# MCU_Power_Supply_Accel.net
KiCad netlist of a schematic drawn in Altium Designer
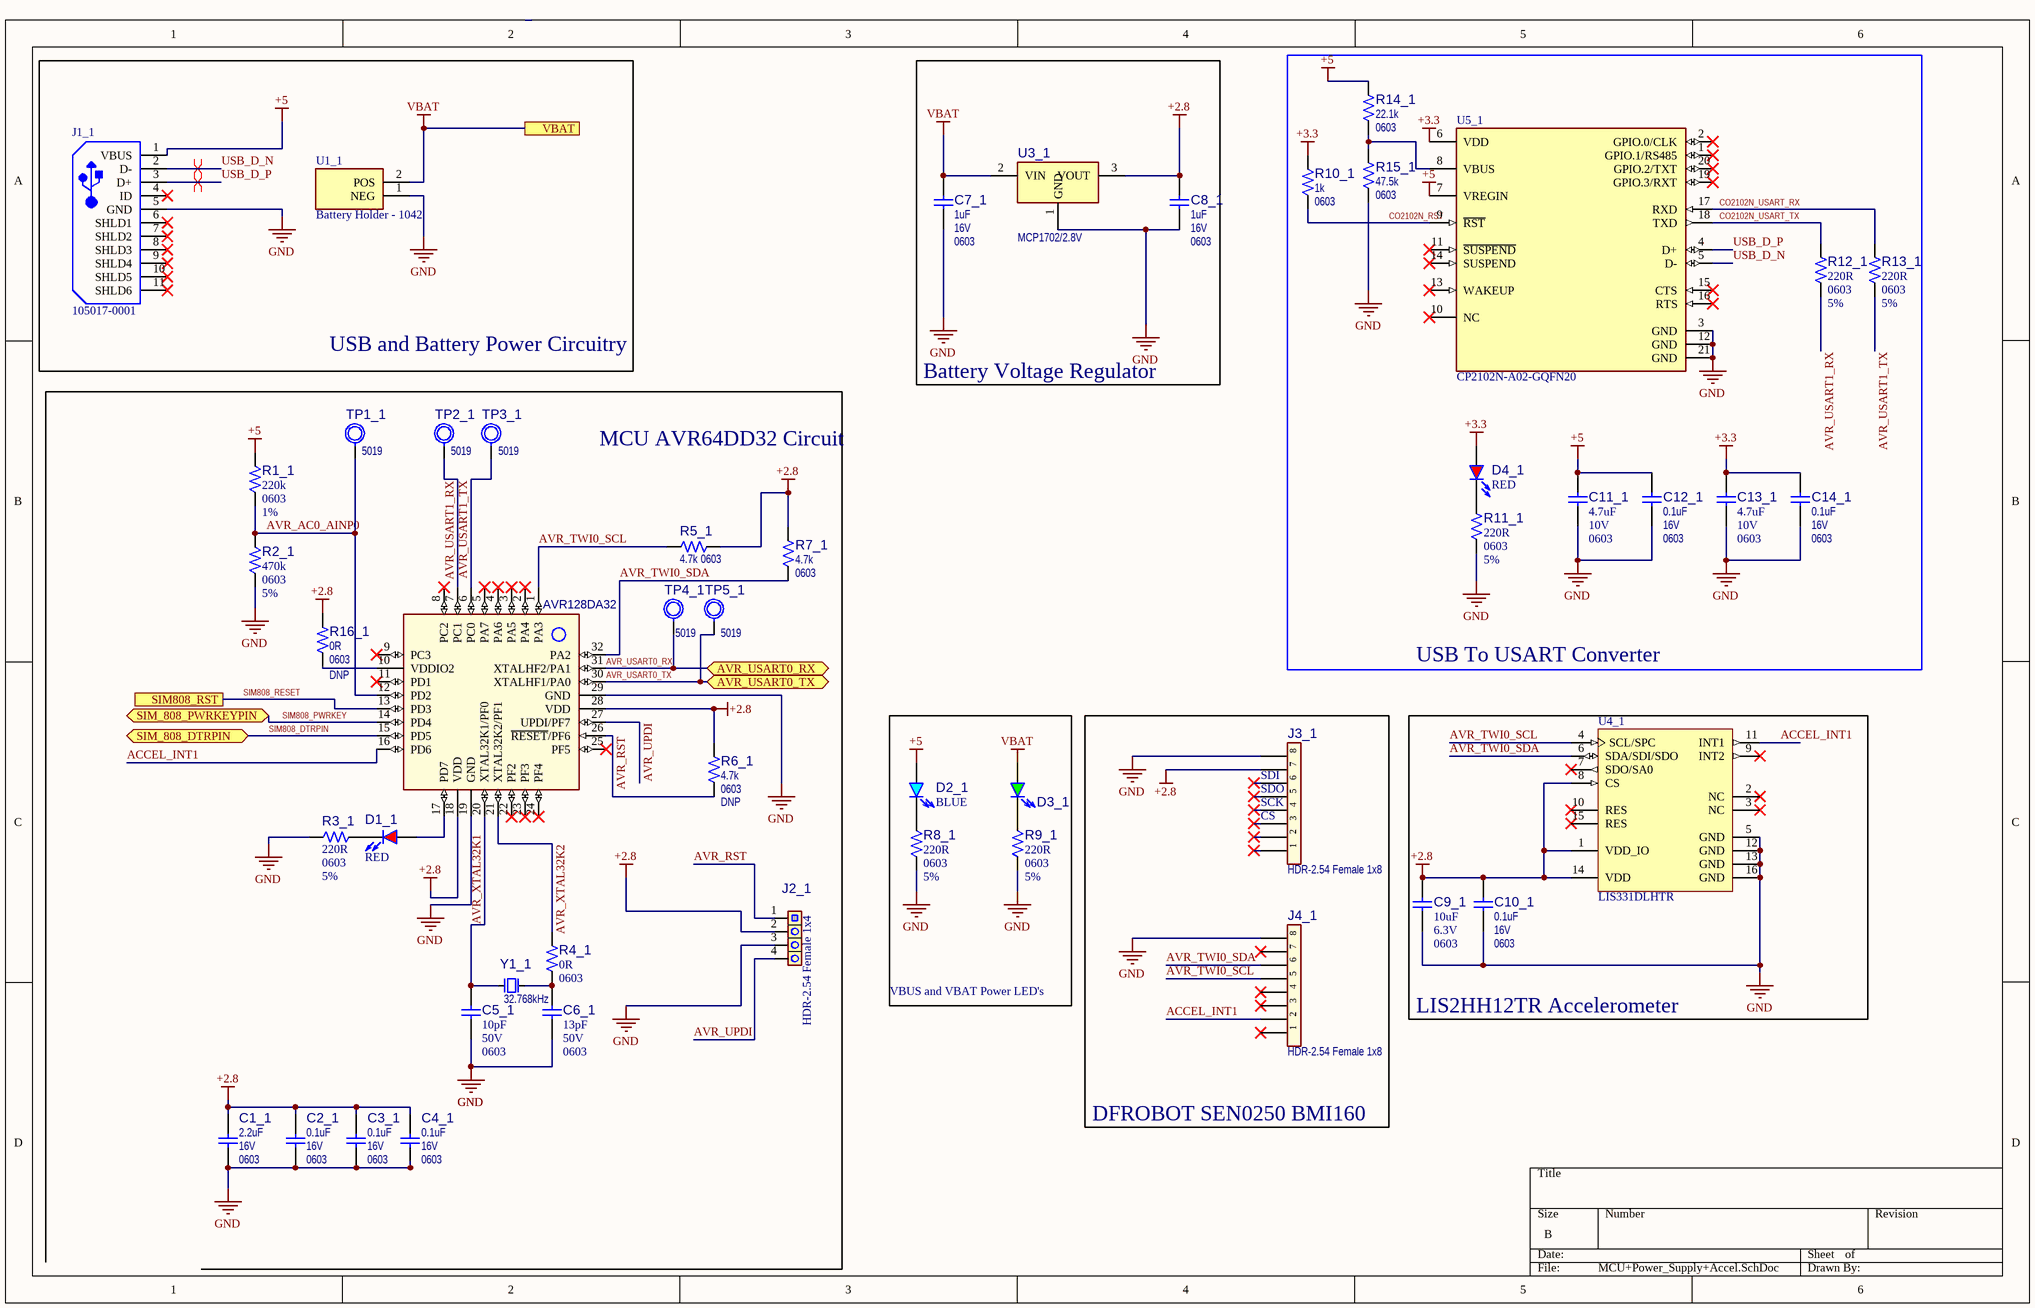
[diagram p0: MCU+Power_Supply+Accel.SchDoc]

(export (version "E")
  (design (tool "Eeschema 10.0.6"))
  (components
    (comp (ref "AVR128DA32")
      (value "AVR128DA32-E/PT")
      (footprint "TQFP-32_7x7")
      (fields (field (name "OWNER") "Simen Tanbergmoen"))
      (libsource (lib "MCHP-CDB-Offline") (part "AVR64DD32 TQFP-32"))
    )
    (comp (ref "C1_1")
      (value "2.2uF")
      (footprint "CAP_C_0603")
      (fields
        (field (name "VOLTAGE") "16V")
        (field (name "PACKAGE") "0603")
        (field (name "TOLERANCE") "10%")
        (field (name "Comment") "Capacitor NP")
      )
      (libsource (lib "MCHP-CDB") (part "Capacitor NP"))
    )
    (comp (ref "C2_1")
      (value "0.1uF")
      (footprint "CAP_C_0603")
      (fields
        (field (name "VOLTAGE") "16V")
        (field (name "PACKAGE") "0603")
        (field (name "TOLERANCE") "10%")
        (field (name "Comment") "Capacitor NP")
        (field (name "OWNER") "Cristian Papuc")
      )
      (libsource (lib "MCHP-CDB") (part "Capacitor NP"))
    )
    (comp (ref "C3_1")
      (value "0.1uF")
      (footprint "CAP_C_0603")
      (fields
        (field (name "VOLTAGE") "16V")
        (field (name "PACKAGE") "0603")
        (field (name "TOLERANCE") "10%")
        (field (name "Comment") "Capacitor NP")
        (field (name "OWNER") "Cristian Papuc")
      )
      (libsource (lib "MCHP-CDB") (part "Capacitor NP"))
    )
    (comp (ref "C4_1")
      (value "0.1uF")
      (footprint "CAP_C_0603")
      (fields
        (field (name "VOLTAGE") "16V")
        (field (name "PACKAGE") "0603")
        (field (name "TOLERANCE") "10%")
        (field (name "Comment") "Capacitor NP")
        (field (name "OWNER") "Cristian Papuc")
      )
      (libsource (lib "MCHP-CDB") (part "Capacitor NP"))
    )
    (comp (ref "C5_1")
      (value "10pF")
      (footprint "CAP_C_0603")
      (fields
        (field (name "VOLTAGE") "50V")
        (field (name "PACKAGE") "0603")
        (field (name "TOLERANCE") "5%")
        (field (name "Comment") "Capacitor NP")
        (field (name "OWNER") "Cristina Salanti")
      )
      (libsource (lib "MCHP-CDB") (part "Capacitor NP"))
    )
    (comp (ref "C6_1")
      (value "13pF")
      (footprint "CAP_C_0603")
      (fields
        (field (name "VOLTAGE") "50V")
        (field (name "PACKAGE") "0603")
        (field (name "TOLERANCE") "2%")
        (field (name "Comment") "Capacitor NP")
        (field (name "OWNER") "Dragos Danaila")
      )
      (libsource (lib "MCHP-CDB") (part "Capacitor NP"))
    )
    (comp (ref "C7_1")
      (value "1uF")
      (footprint "CAP_C_0603")
      (fields
        (field (name "VOLTAGE") "16V")
        (field (name "PACKAGE") "0603")
        (field (name "TOLERANCE") "10%")
        (field (name "Comment") "Capacitor NP")
      )
      (libsource (lib "MCHP-CDB") (part "Capacitor NP"))
    )
    (comp (ref "C8_1")
      (value "1uF")
      (footprint "CAP_C_0603")
      (fields
        (field (name "VOLTAGE") "16V")
        (field (name "PACKAGE") "0603")
        (field (name "TOLERANCE") "10%")
        (field (name "Comment") "Capacitor NP")
      )
      (libsource (lib "MCHP-CDB") (part "Capacitor NP"))
    )
    (comp (ref "C9_1")
      (value "10uF")
      (footprint "CAP_C_0603")
      (fields
        (field (name "VOLTAGE") "6.3V")
        (field (name "PACKAGE") "0603")
        (field (name "TOLERANCE") "20%")
        (field (name "Comment") "Capacitor NP")
      )
      (libsource (lib "MCHP-CDB") (part "Capacitor NP"))
    )
    (comp (ref "C10_1")
      (value "0.1uF")
      (footprint "CAP_C_0603")
      (fields
        (field (name "VOLTAGE") "16V")
        (field (name "PACKAGE") "0603")
        (field (name "TOLERANCE") "10%")
        (field (name "Comment") "Capacitor NP")
        (field (name "OWNER") "Cristian Papuc")
      )
      (libsource (lib "MCHP-CDB") (part "Capacitor NP"))
    )
    (comp (ref "C11_1")
      (value "4.7uF")
      (footprint "CAP_C_0603")
      (fields
        (field (name "VOLTAGE") "10V")
        (field (name "PACKAGE") "0603")
        (field (name "TOLERANCE") "80%")
        (field (name "Comment") "Capacitor NP")
      )
      (libsource (lib "MCHP-CDB") (part "Capacitor NP"))
    )
    (comp (ref "C12_1")
      (value "0.1uF")
      (footprint "CAP_C_0603")
      (fields
        (field (name "VOLTAGE") "16V")
        (field (name "PACKAGE") "0603")
        (field (name "TOLERANCE") "10%")
        (field (name "Comment") "Capacitor NP")
        (field (name "OWNER") "Cristian Papuc")
      )
      (libsource (lib "MCHP-CDB") (part "Capacitor NP"))
    )
    (comp (ref "C13_1")
      (value "4.7uF")
      (footprint "CAP_C_0603")
      (fields
        (field (name "VOLTAGE") "10V")
        (field (name "PACKAGE") "0603")
        (field (name "TOLERANCE") "80%")
        (field (name "Comment") "Capacitor NP")
      )
      (libsource (lib "MCHP-CDB") (part "Capacitor NP"))
    )
    (comp (ref "C14_1")
      (value "0.1uF")
      (footprint "CAP_C_0603")
      (fields
        (field (name "VOLTAGE") "16V")
        (field (name "PACKAGE") "0603")
        (field (name "TOLERANCE") "10%")
        (field (name "Comment") "Capacitor NP")
        (field (name "OWNER") "Cristian Papuc")
      )
      (libsource (lib "MCHP-CDB") (part "Capacitor NP"))
    )
    (comp (ref "D1_1")
      (value "RED")
      (footprint "LED_0603_RED")
      (description "LED")
      (fields (field (name "POWER") "100mW") (field (name "Comment") "LED_red"))
      (libsource (lib "MCHP-CDB") (part "LED_red"))
    )
    (comp (ref "D2_1")
      (value "BLUE")
      (footprint "LED_0603_Blue")
      (description "LED")
      (fields
        (field (name "POWER") "76mW")
        (field (name "Comment") "LED_blue")
        (field (name "OWNER") "Tad Ahlvers")
      )
      (libsource (lib "MCHP-CDB") (part "LED_blue"))
    )
    (comp (ref "D3_1")
      (value "LED_green_true")
      (footprint "LED_0603_Green")
      (description "LED TRUE GREEN")
      (fields (field (name "OWNER") "Ed Kennedy"))
      (libsource (lib "MCHP-CDB") (part "LED_green_true"))
    )
    (comp (ref "D4_1")
      (value "RED")
      (footprint "LED_0603_RED")
      (description "LED")
      (fields (field (name "POWER") "100mW") (field (name "Comment") "LED_red"))
      (libsource (lib "MCHP-CDB") (part "LED_red"))
    )
    (comp (ref "J1_1")
      (value "105017-0001")
      (footprint "USB-MICRO-B_V")
      (fields (field (name "MANUFACTURER") "Molex"))
      (libsource (lib "Altium Content Vault") (part "USB-5-6SHLD"))
    )
    (comp (ref "J2_1")
      (value "HDR-2.54 Female 1x4")
      (footprint "HDR_F_2.54_1x4_U_TH_V_SAM_SSW-104-01-G-S")
      (fields (field (name "Comment") "Header 1x4") (field (name "OWNER") "Randolph Sobrepena"))
      (libsource (lib "MCHP-CDB") (part "Header 1x4"))
    )
    (comp (ref "J3_1")
      (value "HDR-2.54 Female 1x8")
      (footprint "HDR_F_2.54_1x8")
      (description "Header 1x8")
      (fields (field (name "OWNER") "Bogdan P (M91398)"))
      (libsource (lib "MCHP-CDB") (part "Header 1x8"))
    )
    (comp (ref "J4_1")
      (value "HDR-2.54 Female 1x8")
      (footprint "HDR_F_2.54_1x8")
      (description "Header 1x8")
      (fields (field (name "OWNER") "Bogdan P (M91398)"))
      (libsource (lib "MCHP-CDB") (part "Header 1x8"))
    )
    (comp (ref "R1_1")
      (value "220k")
      (footprint "RES_C_0603")
      (description "Resistor")
      (fields
        (field (name "PACKAGE") "0603")
        (field (name "TOLERANCE") "1%")
        (field (name "VOLTAGE") "75V")
        (field (name "POWER") "1/10W")
        (field (name "OWNER") "Adrian M (M91404)")
      )
      (libsource (lib "MCHP-CDB") (part "Resistor"))
    )
    (comp (ref "R2_1")
      (value "470k")
      (footprint "RES_C_0603")
      (description "Resistor")
      (fields
        (field (name "PACKAGE") "0603")
        (field (name "TOLERANCE") "5%")
        (field (name "VOLTAGE") "75V")
        (field (name "POWER") "1/10W")
        (field (name "OWNER") "Adrian T (M91397)")
      )
      (libsource (lib "MCHP-CDB") (part "Resistor"))
    )
    (comp (ref "R3_1")
      (value "220R")
      (footprint "RES_C_0603")
      (description "Resistor")
      (fields
        (field (name "PACKAGE") "0603")
        (field (name "TOLERANCE") "5%")
        (field (name "VOLTAGE") "50V")
        (field (name "POWER") "1/10W")
      )
      (libsource (lib "MCHP-CDB") (part "Resistor"))
    )
    (comp (ref "R4_1")
      (value "0R")
      (footprint "RES_C_0603")
      (description "Resistor")
      (fields
        (field (name "PACKAGE") "0603")
        (field (name "POWER") "1/10W")
        (field (name "OWNER") "Steve Dziaba")
      )
      (libsource (lib "MCHP-CDB") (part "Resistor"))
    )
    (comp (ref "R5_1")
      (value "4.7k")
      (footprint "RES_C_0603")
      (description "Resistor")
      (fields
        (field (name "PACKAGE") "0603")
        (field (name "VOLTAGE") "75V")
        (field (name "POWER") "1/10W")
        (field (name "OWNER") "Bogdan P (M91398)")
      )
      (libsource (lib "MCHP-CDB") (part "Resistor"))
    )
    (comp (ref "R6_1")
      (value "4.7k")
      (footprint "RES_C_0603")
      (description "Resistor")
      (fields
        (field (name "PACKAGE") "0603")
        (field (name "VOLTAGE") "75V")
        (field (name "POWER") "1/10W")
        (field (name "POPULATED") "DNP")
        (field (name "OWNER") "Bogdan P (M91398)")
      )
      (libsource (lib "MCHP-CDB") (part "Resistor"))
    )
    (comp (ref "R7_1")
      (value "4.7k")
      (footprint "RES_C_0603")
      (description "Resistor")
      (fields
        (field (name "PACKAGE") "0603")
        (field (name "VOLTAGE") "75V")
        (field (name "POWER") "1/10W")
        (field (name "OWNER") "Bogdan P (M91398)")
      )
      (libsource (lib "MCHP-CDB") (part "Resistor"))
    )
    (comp (ref "R8_1")
      (value "220R")
      (footprint "RES_C_0603")
      (description "Resistor")
      (fields
        (field (name "PACKAGE") "0603")
        (field (name "TOLERANCE") "5%")
        (field (name "VOLTAGE") "50V")
        (field (name "POWER") "1/10W")
      )
      (libsource (lib "MCHP-CDB") (part "Resistor"))
    )
    (comp (ref "R9_1")
      (value "220R")
      (footprint "RES_C_0603")
      (description "Resistor")
      (fields
        (field (name "PACKAGE") "0603")
        (field (name "TOLERANCE") "5%")
        (field (name "VOLTAGE") "50V")
        (field (name "POWER") "1/10W")
      )
      (libsource (lib "MCHP-CDB") (part "Resistor"))
    )
    (comp (ref "R10_1")
      (value "1k")
      (footprint "RES_C_0603")
      (description "Resistor")
      (fields
        (field (name "PACKAGE") "0603")
        (field (name "VOLTAGE") "75V")
        (field (name "POWER") "1/10W")
        (field (name "OWNER") "Tad Ahlvers")
      )
      (libsource (lib "MCHP-CDB") (part "Resistor"))
    )
    (comp (ref "R11_1")
      (value "220R")
      (footprint "RES_C_0603")
      (description "Resistor")
      (fields
        (field (name "PACKAGE") "0603")
        (field (name "TOLERANCE") "5%")
        (field (name "VOLTAGE") "50V")
        (field (name "POWER") "1/10W")
      )
      (libsource (lib "MCHP-CDB") (part "Resistor"))
    )
    (comp (ref "R12_1")
      (value "220R")
      (footprint "RES_C_0603")
      (description "Resistor")
      (fields
        (field (name "PACKAGE") "0603")
        (field (name "TOLERANCE") "5%")
        (field (name "VOLTAGE") "50V")
        (field (name "POWER") "1/10W")
      )
      (libsource (lib "MCHP-CDB") (part "Resistor"))
    )
    (comp (ref "R13_1")
      (value "220R")
      (footprint "RES_C_0603")
      (description "Resistor")
      (fields
        (field (name "PACKAGE") "0603")
        (field (name "TOLERANCE") "5%")
        (field (name "VOLTAGE") "50V")
        (field (name "POWER") "1/10W")
      )
      (libsource (lib "MCHP-CDB") (part "Resistor"))
    )
    (comp (ref "R14_1")
      (value "22.1k")
      (footprint "RES_C_0603")
      (description "Resistor")
      (fields
        (field (name "PACKAGE") "0603")
        (field (name "VOLTAGE") "75V")
        (field (name "POWER") "1/10W")
        (field (name "OWNER") "Kamatchi Sundaresan")
      )
      (libsource (lib "MCHP-CDB") (part "Resistor"))
    )
    (comp (ref "R15_1")
      (value "47.5k")
      (footprint "RES_C_0603")
      (description "Resistor")
      (fields
        (field (name "PACKAGE") "0603")
        (field (name "POWER") "1/10W")
        (field (name "OWNER") "Sam Charles")
      )
      (libsource (lib "MCHP-CDB") (part "Resistor"))
    )
    (comp (ref "R16_1")
      (value "0R")
      (footprint "RES_C_0603")
      (description "Resistor")
      (fields
        (field (name "PACKAGE") "0603")
        (field (name "POWER") "1/10W")
        (field (name "POPULATED") "DNP")
        (field (name "OWNER") "Steve Dziaba")
      )
      (libsource (lib "MCHP-CDB") (part "Resistor"))
    )
    (comp (ref "TP1_1")
      (value "5019")
      (footprint "TP_3.8x2.03_SMD")
      (description "Test Point")
      (fields (field (name "OWNER") "Jairuz Agang-ang"))
      (libsource (lib "MCHP-CDB") (part "Test Point"))
    )
    (comp (ref "TP2_1")
      (value "5019")
      (footprint "TP_3.8x2.03_SMD")
      (description "Test Point")
      (fields (field (name "OWNER") "Jairuz Agang-ang"))
      (libsource (lib "MCHP-CDB") (part "Test Point"))
    )
    (comp (ref "TP3_1")
      (value "5019")
      (footprint "TP_3.8x2.03_SMD")
      (description "Test Point")
      (fields (field (name "OWNER") "Jairuz Agang-ang"))
      (libsource (lib "MCHP-CDB") (part "Test Point"))
    )
    (comp (ref "TP4_1")
      (value "5019")
      (footprint "TP_3.8x2.03_SMD")
      (description "Test Point")
      (fields (field (name "OWNER") "Jairuz Agang-ang"))
      (libsource (lib "MCHP-CDB") (part "Test Point"))
    )
    (comp (ref "TP5_1")
      (value "5019")
      (footprint "TP_3.8x2.03_SMD")
      (description "Test Point")
      (fields (field (name "OWNER") "Jairuz Agang-ang"))
      (libsource (lib "MCHP-CDB") (part "Test Point"))
    )
    (comp (ref "U1_1")
      (value "Battery Holder - 1042")
      (footprint "SamacSys:KEYSTONE-1042")
      (description "Undefined or Miscellaneous")
      (fields (field (name "MANUFACTURER_PART_NUMBER") "1042") (field (name "MOUSER PART NUMBER") "534-1042"))
      (libsource (lib "*") (part "1042"))
    )
    (comp (ref "U3_1")
      (value "MCP1702/2.8V")
      (footprint "SOT-89-3")
      (description "LDO")
      (fields (field (name "Comment") "MCP170X SOT-89-3_TO-92-3"))
      (libsource (lib "MCHP-CDB") (part "MCP170X SOT-89-3_TO-92-3"))
    )
    (comp (ref "U4_1")
      (value "LIS331DLHTR")
      (footprint "STM-LGA16-3X3X1")
      (fields (field (name "MANUFACTURER") "STMicroelectronics"))
      (libsource (lib "Altium Content Vault") (part "SEN-MOT-LIS331DL-16"))
    )
    (comp (ref "U5_1")
      (value "CP2102N-A02-GQFN20")
      (footprint "FP-CP2102N-A02-GQFN20-MFG")
      (description "IC USB TO UART BRIDGE QFN20")
      (libsource (lib "Altium Content Vault") (part "535e9eb0fa6e07ebb008498c6833ade"))
    )
    (comp (ref "Y1_1")
      (value "32.768kHz")
      (footprint "CRYSTAL_FX135A_L3.2W1.5H0.9")
      (description "Crystal")
      (fields
        (field (name "TOLERANCE") "20ppm")
        (field (name "Comment") "Crystal 2 Pins")
        (field (name "OWNER") "Jesus Aviles")
      )
      (libsource (lib "MCHP-CDB") (part "Crystal 2 Pins"))
    )
  )
  (nets
    (net (code "1") (name "+2.8") (class "Default")
      (node (ref "AVR128DA32") (pin "18") (pinfunction "VDD_18") (pintype "power_in"))
      (node (ref "AVR128DA32") (pin "28") (pinfunction "VDD_28") (pintype "power_in"))
      (node (ref "C10_1") (pin "2") (pinfunction "2_2") (pintype "passive"))
      (node (ref "C1_1") (pin "2") (pinfunction "2_2") (pintype "passive"))
      (node (ref "C2_1") (pin "2") (pinfunction "2_2") (pintype "passive"))
      (node (ref "C3_1") (pin "2") (pinfunction "2_2") (pintype "passive"))
      (node (ref "C4_1") (pin "2") (pinfunction "2_2") (pintype "passive"))
      (node (ref "C8_1") (pin "2") (pinfunction "2_2") (pintype "passive"))
      (node (ref "C9_1") (pin "2") (pinfunction "2_2") (pintype "passive"))
      (node (ref "J2_1") (pin "2") (pinfunction "2_2") (pintype "passive"))
      (node (ref "J3_1") (pin "7") (pinfunction "7_7") (pintype "passive"))
      (node (ref "R16_1") (pin "1") (pinfunction "1_1") (pintype "passive"))
      (node (ref "R5_1") (pin "2") (pinfunction "2_2") (pintype "passive"))
      (node (ref "R6_1") (pin "2") (pinfunction "2_2") (pintype "passive"))
      (node (ref "R7_1") (pin "2") (pinfunction "2_2") (pintype "passive"))
      (node (ref "U3_1") (pin "3") (pinfunction "VOUT_3") (pintype "power_in"))
      (node (ref "U4_1") (pin "1") (pinfunction "VDD_IO_1") (pintype "power_in"))
      (node (ref "U4_1") (pin "14") (pinfunction "VDD_14") (pintype "power_in"))
      (node (ref "U4_1") (pin "8") (pinfunction "CS_8") (pintype "input"))
    )
    (net (code "2") (name "+3.3") (class "Default")
      (node (ref "C13_1") (pin "2") (pinfunction "2_2") (pintype "passive"))
      (node (ref "C14_1") (pin "2") (pinfunction "2_2") (pintype "passive"))
      (node (ref "D4_1") (pin "1") (pinfunction "A_1") (pintype "passive"))
      (node (ref "R10_1") (pin "2") (pinfunction "2_2") (pintype "passive"))
      (node (ref "U5_1") (pin "6") (pinfunction "VDD_6") (pintype "power_in"))
    )
    (net (code "3") (name "+5") (class "Default")
      (node (ref "C11_1") (pin "2") (pinfunction "2_2") (pintype "passive"))
      (node (ref "C12_1") (pin "2") (pinfunction "2_2") (pintype "passive"))
      (node (ref "D2_1") (pin "1") (pinfunction "A_1") (pintype "passive"))
      (node (ref "J1_1") (pin "1") (pinfunction "VBUS_1") (pintype "passive"))
      (node (ref "R14_1") (pin "2") (pinfunction "2_2") (pintype "passive"))
      (node (ref "R1_1") (pin "2") (pinfunction "2_2") (pintype "passive"))
      (node (ref "U5_1") (pin "7") (pinfunction "VREGIN_7") (pintype "power_in"))
    )
    (net (code "4") (name "/ACCEL_INT1") (class "Default")
      (node (ref "AVR128DA32") (pin "16") (pinfunction "PD6_16") (pintype "bidirectional"))
      (node (ref "J4_1") (pin "2") (pinfunction "2_2") (pintype "passive"))
      (node (ref "U4_1") (pin "11") (pinfunction "INT1_11") (pintype "output"))
    )
    (net (code "5") (name "/AVR_AC0_AINP0") (class "Default")
      (node (ref "AVR128DA32") (pin "12") (pinfunction "PD2_12") (pintype "bidirectional"))
      (node (ref "R1_1") (pin "1") (pinfunction "1_1") (pintype "passive"))
      (node (ref "R2_1") (pin "1") (pinfunction "1_1") (pintype "passive"))
      (node (ref "TP1_1") (pin "1") (pinfunction "1_1") (pintype "passive"))
    )
    (net (code "6") (name "/AVR_RST") (class "Default")
      (node (ref "AVR128DA32") (pin "26") (pinfunction "~{RESET}/PF6_26") (pintype "input"))
      (node (ref "J2_1") (pin "1") (pinfunction "1_1") (pintype "passive"))
      (node (ref "R6_1") (pin "1") (pinfunction "1_1") (pintype "passive"))
    )
    (net (code "7") (name "/AVR_TWI0_SCL") (class "Default")
      (node (ref "AVR128DA32") (pin "1") (pinfunction "PA3_1") (pintype "bidirectional"))
      (node (ref "J4_1") (pin "5") (pinfunction "5_5") (pintype "passive"))
      (node (ref "R5_1") (pin "1") (pinfunction "1_1") (pintype "passive"))
      (node (ref "U4_1") (pin "4") (pinfunction "SCL/SPC_4") (pintype "input"))
    )
    (net (code "8") (name "/AVR_TWI0_SDA") (class "Default")
      (node (ref "AVR128DA32") (pin "32") (pinfunction "PA2_32") (pintype "bidirectional"))
      (node (ref "J4_1") (pin "6") (pinfunction "6_6") (pintype "passive"))
      (node (ref "R7_1") (pin "1") (pinfunction "1_1") (pintype "passive"))
      (node (ref "U4_1") (pin "6") (pinfunction "SDA/SDI/SDO_6") (pintype "bidirectional"))
    )
    (net (code "9") (name "/AVR_UPDI") (class "Default")
      (node (ref "AVR128DA32") (pin "27") (pinfunction "UPDI/PF7_27") (pintype "bidirectional"))
      (node (ref "J2_1") (pin "4") (pinfunction "4_4") (pintype "passive"))
    )
    (net (code "10") (name "/AVR_USART0_RX") (class "Default")
      (node (ref "AVR128DA32") (pin "31") (pinfunction "XTALHF2/PA1_31") (pintype "bidirectional"))
      (node (ref "TP4_1") (pin "1") (pinfunction "1_1") (pintype "passive"))
    )
    (net (code "11") (name "/AVR_USART0_TX") (class "Default")
      (node (ref "AVR128DA32") (pin "30") (pinfunction "XTALHF1/PA0_30") (pintype "bidirectional"))
      (node (ref "TP5_1") (pin "1") (pinfunction "1_1") (pintype "passive"))
    )
    (net (code "12") (name "/AVR_USART1_RX") (class "Default")
      (node (ref "AVR128DA32") (pin "7") (pinfunction "PC1_7") (pintype "bidirectional"))
      (node (ref "R12_1") (pin "1") (pinfunction "1_1") (pintype "passive"))
      (node (ref "TP2_1") (pin "1") (pinfunction "1_1") (pintype "passive"))
    )
    (net (code "13") (name "/AVR_USART1_TX") (class "Default")
      (node (ref "AVR128DA32") (pin "6") (pinfunction "PC0_6") (pintype "bidirectional"))
      (node (ref "R13_1") (pin "1") (pinfunction "1_1") (pintype "passive"))
      (node (ref "TP3_1") (pin "1") (pinfunction "1_1") (pintype "passive"))
    )
    (net (code "14") (name "/AVR_XTAL32K1") (class "Default")
      (node (ref "AVR128DA32") (pin "20") (pinfunction "XTAL32K1/PF0_20") (pintype "bidirectional"))
      (node (ref "C5_1") (pin "2") (pinfunction "2_2") (pintype "passive"))
      (node (ref "Y1_1") (pin "1") (pinfunction "Osc1_1") (pintype "passive"))
    )
    (net (code "15") (name "/AVR_XTAL32K2") (class "Default")
      (node (ref "AVR128DA32") (pin "21") (pinfunction "XTAL32K2/PF1_21") (pintype "bidirectional"))
      (node (ref "R4_1") (pin "2") (pinfunction "2_2") (pintype "passive"))
    )
    (net (code "16") (name "/CO2102N_RST") (class "Default")
      (node (ref "R10_1") (pin "1") (pinfunction "1_1") (pintype "passive"))
      (node (ref "U5_1") (pin "9") (pinfunction "~{RST}_9") (pintype "input"))
    )
    (net (code "17") (name "/CO2102N_USART_RX") (class "Default")
      (node (ref "R13_1") (pin "2") (pinfunction "2_2") (pintype "passive"))
      (node (ref "U5_1") (pin "17") (pinfunction "RXD_17") (pintype "input"))
    )
    (net (code "18") (name "/CO2102N_USART_TX") (class "Default")
      (node (ref "R12_1") (pin "2") (pinfunction "2_2") (pintype "passive"))
      (node (ref "U5_1") (pin "18") (pinfunction "TXD_18") (pintype "output"))
    )
    (net (code "19") (name "/SIM808_DTRPIN") (class "Default")
      (node (ref "AVR128DA32") (pin "15") (pinfunction "PD5_15") (pintype "bidirectional"))
    )
    (net (code "20") (name "/SIM808_PWRKEY") (class "Default")
      (node (ref "AVR128DA32") (pin "14") (pinfunction "PD4_14") (pintype "bidirectional"))
    )
    (net (code "21") (name "/SIM808_RESET") (class "Default")
      (node (ref "AVR128DA32") (pin "13") (pinfunction "PD3_13") (pintype "bidirectional"))
    )
    (net (code "22") (name "/USB_D_N") (class "Default")
      (node (ref "J1_1") (pin "2") (pinfunction "D-_2") (pintype "passive"))
      (node (ref "U5_1") (pin "5") (pinfunction "D-_5") (pintype "bidirectional"))
    )
    (net (code "23") (name "/USB_D_P") (class "Default")
      (node (ref "J1_1") (pin "3") (pinfunction "D+_3") (pintype "passive"))
      (node (ref "U5_1") (pin "4") (pinfunction "D+_4") (pintype "bidirectional"))
    )
    (net (code "24") (name "GND") (class "Default")
      (node (ref "AVR128DA32") (pin "19") (pinfunction "GND_19") (pintype "power_in"))
      (node (ref "AVR128DA32") (pin "29") (pinfunction "GND_29") (pintype "power_in"))
      (node (ref "C10_1") (pin "1") (pinfunction "1_1") (pintype "passive"))
      (node (ref "C11_1") (pin "1") (pinfunction "1_1") (pintype "passive"))
      (node (ref "C12_1") (pin "1") (pinfunction "1_1") (pintype "passive"))
      (node (ref "C13_1") (pin "1") (pinfunction "1_1") (pintype "passive"))
      (node (ref "C14_1") (pin "1") (pinfunction "1_1") (pintype "passive"))
      (node (ref "C1_1") (pin "1") (pinfunction "1_1") (pintype "passive"))
      (node (ref "C2_1") (pin "1") (pinfunction "1_1") (pintype "passive"))
      (node (ref "C3_1") (pin "1") (pinfunction "1_1") (pintype "passive"))
      (node (ref "C4_1") (pin "1") (pinfunction "1_1") (pintype "passive"))
      (node (ref "C5_1") (pin "1") (pinfunction "1_1") (pintype "passive"))
      (node (ref "C6_1") (pin "1") (pinfunction "1_1") (pintype "passive"))
      (node (ref "C7_1") (pin "1") (pinfunction "1_1") (pintype "passive"))
      (node (ref "C8_1") (pin "1") (pinfunction "1_1") (pintype "passive"))
      (node (ref "C9_1") (pin "1") (pinfunction "1_1") (pintype "passive"))
      (node (ref "J1_1") (pin "5") (pinfunction "GND_5") (pintype "passive"))
      (node (ref "J2_1") (pin "3") (pinfunction "3_3") (pintype "passive"))
      (node (ref "J3_1") (pin "8") (pinfunction "8_8") (pintype "passive"))
      (node (ref "J4_1") (pin "8") (pinfunction "8_8") (pintype "passive"))
      (node (ref "R11_1") (pin "1") (pinfunction "1_1") (pintype "passive"))
      (node (ref "R15_1") (pin "1") (pinfunction "1_1") (pintype "passive"))
      (node (ref "R2_1") (pin "2") (pinfunction "2_2") (pintype "passive"))
      (node (ref "R3_1") (pin "2") (pinfunction "2_2") (pintype "passive"))
      (node (ref "R8_1") (pin "1") (pinfunction "1_1") (pintype "passive"))
      (node (ref "R9_1") (pin "1") (pinfunction "1_1") (pintype "passive"))
      (node (ref "U1_1") (pin "1") (pinfunction "NEG_1") (pintype "passive"))
      (node (ref "U3_1") (pin "1") (pinfunction "GND_1") (pintype "power_in"))
      (node (ref "U4_1") (pin "12") (pinfunction "GND_12") (pintype "power_in"))
      (node (ref "U4_1") (pin "13") (pinfunction "GND_13") (pintype "power_in"))
      (node (ref "U4_1") (pin "16") (pinfunction "GND_16") (pintype "power_in"))
      (node (ref "U4_1") (pin "5") (pinfunction "GND_5") (pintype "power_in"))
      (node (ref "U5_1") (pin "12") (pinfunction "GND_12") (pintype "power_in"))
      (node (ref "U5_1") (pin "21") (pinfunction "GND_21") (pintype "power_in"))
      (node (ref "U5_1") (pin "3") (pinfunction "GND_3") (pintype "power_in"))
    )
    (net (code "25") (name "Net-(AVR128DA32-PD7)") (class "Default")
      (node (ref "AVR128DA32") (pin "17") (pinfunction "PD7_17") (pintype "bidirectional"))
      (node (ref "D1_1") (pin "1") (pinfunction "A_1") (pintype "passive"))
    )
    (net (code "26") (name "Net-(AVR128DA32-VDDIO2)") (class "Default")
      (node (ref "AVR128DA32") (pin "10") (pinfunction "VDDIO2_10") (pintype "power_in"))
      (node (ref "R16_1") (pin "2") (pinfunction "2_2") (pintype "passive"))
    )
    (net (code "27") (name "Net-(D1_1-K)") (class "Default")
      (node (ref "D1_1") (pin "2") (pinfunction "K_2") (pintype "passive"))
      (node (ref "R3_1") (pin "1") (pinfunction "1_1") (pintype "passive"))
    )
    (net (code "28") (name "Net-(D2_1-K)") (class "Default")
      (node (ref "D2_1") (pin "2") (pinfunction "K_2") (pintype "passive"))
      (node (ref "R8_1") (pin "2") (pinfunction "2_2") (pintype "passive"))
    )
    (net (code "29") (name "Net-(D3_1-K)") (class "Default")
      (node (ref "D3_1") (pin "2") (pinfunction "K_2") (pintype "passive"))
      (node (ref "R9_1") (pin "2") (pinfunction "2_2") (pintype "passive"))
    )
    (net (code "30") (name "Net-(D4_1-K)") (class "Default")
      (node (ref "D4_1") (pin "2") (pinfunction "K_2") (pintype "passive"))
      (node (ref "R11_1") (pin "2") (pinfunction "2_2") (pintype "passive"))
    )
    (net (code "31") (name "Net-(U5_1-VBUS)") (class "Default")
      (node (ref "R14_1") (pin "1") (pinfunction "1_1") (pintype "passive"))
      (node (ref "R15_1") (pin "2") (pinfunction "2_2") (pintype "passive"))
      (node (ref "U5_1") (pin "8") (pinfunction "VBUS_8") (pintype "power_in"))
    )
    (net (code "32") (name "Net-(Y1_1-Osc2)") (class "Default")
      (node (ref "C6_1") (pin "2") (pinfunction "2_2") (pintype "passive"))
      (node (ref "R4_1") (pin "1") (pinfunction "1_1") (pintype "passive"))
      (node (ref "Y1_1") (pin "2") (pinfunction "Osc2_2") (pintype "passive"))
    )
    (net (code "33") (name "VBAT") (class "Default")
      (node (ref "C7_1") (pin "2") (pinfunction "2_2") (pintype "passive"))
      (node (ref "D3_1") (pin "1") (pinfunction "A_1") (pintype "passive"))
      (node (ref "U1_1") (pin "2") (pinfunction "POS_2") (pintype "passive"))
      (node (ref "U3_1") (pin "2") (pinfunction "VIN_2") (pintype "power_in"))
    )
    (net (code "34") (name "unconnected-(AVR128DA32-PA4-Pad2)") (class "Default")
      (node (ref "AVR128DA32") (pin "2") (pinfunction "PA4_2") (pintype "bidirectional+no_connect"))
    )
    (net (code "35") (name "unconnected-(AVR128DA32-PA5-Pad3)") (class "Default")
      (node (ref "AVR128DA32") (pin "3") (pinfunction "PA5_3") (pintype "bidirectional+no_connect"))
    )
    (net (code "36") (name "unconnected-(AVR128DA32-PA6-Pad4)") (class "Default")
      (node (ref "AVR128DA32") (pin "4") (pinfunction "PA6_4") (pintype "bidirectional+no_connect"))
    )
    (net (code "37") (name "unconnected-(AVR128DA32-PA7-Pad5)") (class "Default")
      (node (ref "AVR128DA32") (pin "5") (pinfunction "PA7_5") (pintype "bidirectional+no_connect"))
    )
    (net (code "38") (name "unconnected-(AVR128DA32-PC2-Pad8)") (class "Default")
      (node (ref "AVR128DA32") (pin "8") (pinfunction "PC2_8") (pintype "bidirectional+no_connect"))
    )
    (net (code "39") (name "unconnected-(AVR128DA32-PC3-Pad9)") (class "Default")
      (node (ref "AVR128DA32") (pin "9") (pinfunction "PC3_9") (pintype "bidirectional+no_connect"))
    )
    (net (code "40") (name "unconnected-(AVR128DA32-PD1-Pad11)") (class "Default")
      (node (ref "AVR128DA32") (pin "11") (pinfunction "PD1_11") (pintype "bidirectional+no_connect"))
    )
    (net (code "41") (name "unconnected-(AVR128DA32-PF2-Pad22)") (class "Default")
      (node (ref "AVR128DA32") (pin "22") (pinfunction "PF2_22") (pintype "bidirectional+no_connect"))
    )
    (net (code "42") (name "unconnected-(AVR128DA32-PF3-Pad23)") (class "Default")
      (node (ref "AVR128DA32") (pin "23") (pinfunction "PF3_23") (pintype "bidirectional+no_connect"))
    )
    (net (code "43") (name "unconnected-(AVR128DA32-PF4-Pad24)") (class "Default")
      (node (ref "AVR128DA32") (pin "24") (pinfunction "PF4_24") (pintype "bidirectional+no_connect"))
    )
    (net (code "44") (name "unconnected-(AVR128DA32-PF5-Pad25)") (class "Default")
      (node (ref "AVR128DA32") (pin "25") (pinfunction "PF5_25") (pintype "bidirectional+no_connect"))
    )
    (net (code "45") (name "unconnected-(J1_1-ID-Pad4)") (class "Default")
      (node (ref "J1_1") (pin "4") (pinfunction "ID_4") (pintype "passive+no_connect"))
    )
    (net (code "46") (name "unconnected-(J1_1-SHLD1-Pad6)") (class "Default")
      (node (ref "J1_1") (pin "6") (pinfunction "SHLD1_6") (pintype "passive+no_connect"))
    )
    (net (code "47") (name "unconnected-(J1_1-SHLD2-Pad7)") (class "Default")
      (node (ref "J1_1") (pin "7") (pinfunction "SHLD2_7") (pintype "passive+no_connect"))
    )
    (net (code "48") (name "unconnected-(J1_1-SHLD3-Pad8)") (class "Default")
      (node (ref "J1_1") (pin "8") (pinfunction "SHLD3_8") (pintype "passive+no_connect"))
    )
    (net (code "49") (name "unconnected-(J1_1-SHLD4-Pad9)") (class "Default")
      (node (ref "J1_1") (pin "9") (pinfunction "SHLD4_9") (pintype "passive+no_connect"))
    )
    (net (code "50") (name "unconnected-(J1_1-SHLD5-Pad10)") (class "Default")
      (node (ref "J1_1") (pin "10") (pinfunction "SHLD5_10") (pintype "passive+no_connect"))
    )
    (net (code "51") (name "unconnected-(J1_1-SHLD6-Pad11)") (class "Default")
      (node (ref "J1_1") (pin "11") (pinfunction "SHLD6_11") (pintype "passive+no_connect"))
    )
    (net (code "52") (name "unconnected-(J3_1-Pad1)") (class "Default")
      (node (ref "J3_1") (pin "1") (pinfunction "1_1") (pintype "passive+no_connect"))
    )
    (net (code "53") (name "unconnected-(J3_1-Pad2)") (class "Default")
      (node (ref "J3_1") (pin "2") (pinfunction "2_2") (pintype "passive+no_connect"))
    )
    (net (code "54") (name "unconnected-(J3_1-Pad3)") (class "Default")
      (node (ref "J3_1") (pin "3") (pinfunction "3_3") (pintype "passive+no_connect"))
    )
    (net (code "55") (name "unconnected-(J3_1-Pad4)") (class "Default")
      (node (ref "J3_1") (pin "4") (pinfunction "4_4") (pintype "passive+no_connect"))
    )
    (net (code "56") (name "unconnected-(J3_1-Pad5)") (class "Default")
      (node (ref "J3_1") (pin "5") (pinfunction "5_5") (pintype "passive+no_connect"))
    )
    (net (code "57") (name "unconnected-(J3_1-Pad6)") (class "Default")
      (node (ref "J3_1") (pin "6") (pinfunction "6_6") (pintype "passive+no_connect"))
    )
    (net (code "58") (name "unconnected-(J4_1-Pad1)") (class "Default")
      (node (ref "J4_1") (pin "1") (pinfunction "1_1") (pintype "passive+no_connect"))
    )
    (net (code "59") (name "unconnected-(J4_1-Pad3)") (class "Default")
      (node (ref "J4_1") (pin "3") (pinfunction "3_3") (pintype "passive+no_connect"))
    )
    (net (code "60") (name "unconnected-(J4_1-Pad4)") (class "Default")
      (node (ref "J4_1") (pin "4") (pinfunction "4_4") (pintype "passive+no_connect"))
    )
    (net (code "61") (name "unconnected-(J4_1-Pad7)") (class "Default")
      (node (ref "J4_1") (pin "7") (pinfunction "7_7") (pintype "passive+no_connect"))
    )
    (net (code "62") (name "unconnected-(U4_1-INT2-Pad9)") (class "Default")
      (node (ref "U4_1") (pin "9") (pinfunction "INT2_9") (pintype "output+no_connect"))
    )
    (net (code "63") (name "unconnected-(U4_1-NC-Pad2)") (class "Default")
      (node (ref "U4_1") (pin "2") (pinfunction "NC_2") (pintype "passive+no_connect"))
    )
    (net (code "64") (name "unconnected-(U4_1-NC-Pad3)") (class "Default")
      (node (ref "U4_1") (pin "3") (pinfunction "NC_3") (pintype "passive+no_connect"))
    )
    (net (code "65") (name "unconnected-(U4_1-RES-Pad10)") (class "Default")
      (node (ref "U4_1") (pin "10") (pinfunction "RES_10") (pintype "passive+no_connect"))
    )
    (net (code "66") (name "unconnected-(U4_1-RES-Pad15)") (class "Default")
      (node (ref "U4_1") (pin "15") (pinfunction "RES_15") (pintype "passive+no_connect"))
    )
    (net (code "67") (name "unconnected-(U4_1-SDO{slash}SA0-Pad7)") (class "Default")
      (node (ref "U4_1") (pin "7") (pinfunction "SDO/SA0_7") (pintype "output+no_connect"))
    )
    (net (code "68") (name "unconnected-(U5_1-CTS-Pad15)") (class "Default")
      (node (ref "U5_1") (pin "15") (pinfunction "CTS_15") (pintype "input+no_connect"))
    )
    (net (code "69") (name "unconnected-(U5_1-GPIO.0{slash}CLK-Pad2)") (class "Default")
      (node (ref "U5_1") (pin "2") (pinfunction "GPIO.0/CLK_2") (pintype "bidirectional+no_connect"))
    )
    (net (code "70") (name "unconnected-(U5_1-GPIO.1{slash}RS485-Pad1)") (class "Default")
      (node (ref "U5_1") (pin "1") (pinfunction "GPIO.1/RS485_1") (pintype "bidirectional+no_connect"))
    )
    (net (code "71") (name "unconnected-(U5_1-GPIO.2{slash}TXT-Pad20)") (class "Default")
      (node (ref "U5_1") (pin "20") (pinfunction "GPIO.2/TXT_20") (pintype "bidirectional+no_connect"))
    )
    (net (code "72") (name "unconnected-(U5_1-GPIO.3{slash}RXT-Pad19)") (class "Default")
      (node (ref "U5_1") (pin "19") (pinfunction "GPIO.3/RXT_19") (pintype "bidirectional+no_connect"))
    )
    (net (code "73") (name "unconnected-(U5_1-NC-Pad10)") (class "Default")
      (node (ref "U5_1") (pin "10") (pinfunction "NC_10") (pintype "passive+no_connect"))
    )
    (net (code "74") (name "unconnected-(U5_1-RTS-Pad16)") (class "Default")
      (node (ref "U5_1") (pin "16") (pinfunction "RTS_16") (pintype "input+no_connect"))
    )
    (net (code "75") (name "unconnected-(U5_1-SUSPEND-Pad14)") (class "Default")
      (node (ref "U5_1") (pin "14") (pinfunction "SUSPEND_14") (pintype "input+no_connect"))
    )
    (net (code "76") (name "unconnected-(U5_1-WAKEUP-Pad13)") (class "Default")
      (node (ref "U5_1") (pin "13") (pinfunction "WAKEUP_13") (pintype "input+no_connect"))
    )
    (net (code "77") (name "unconnected-(U5_1-~{SUSPEND}-Pad11)") (class "Default")
      (node (ref "U5_1") (pin "11") (pinfunction "~{SUSPEND}_11") (pintype "input+no_connect"))
    )
  )
)
